# darwin-upper.net
KiCad netlist of a schematic drawn in EAGLE
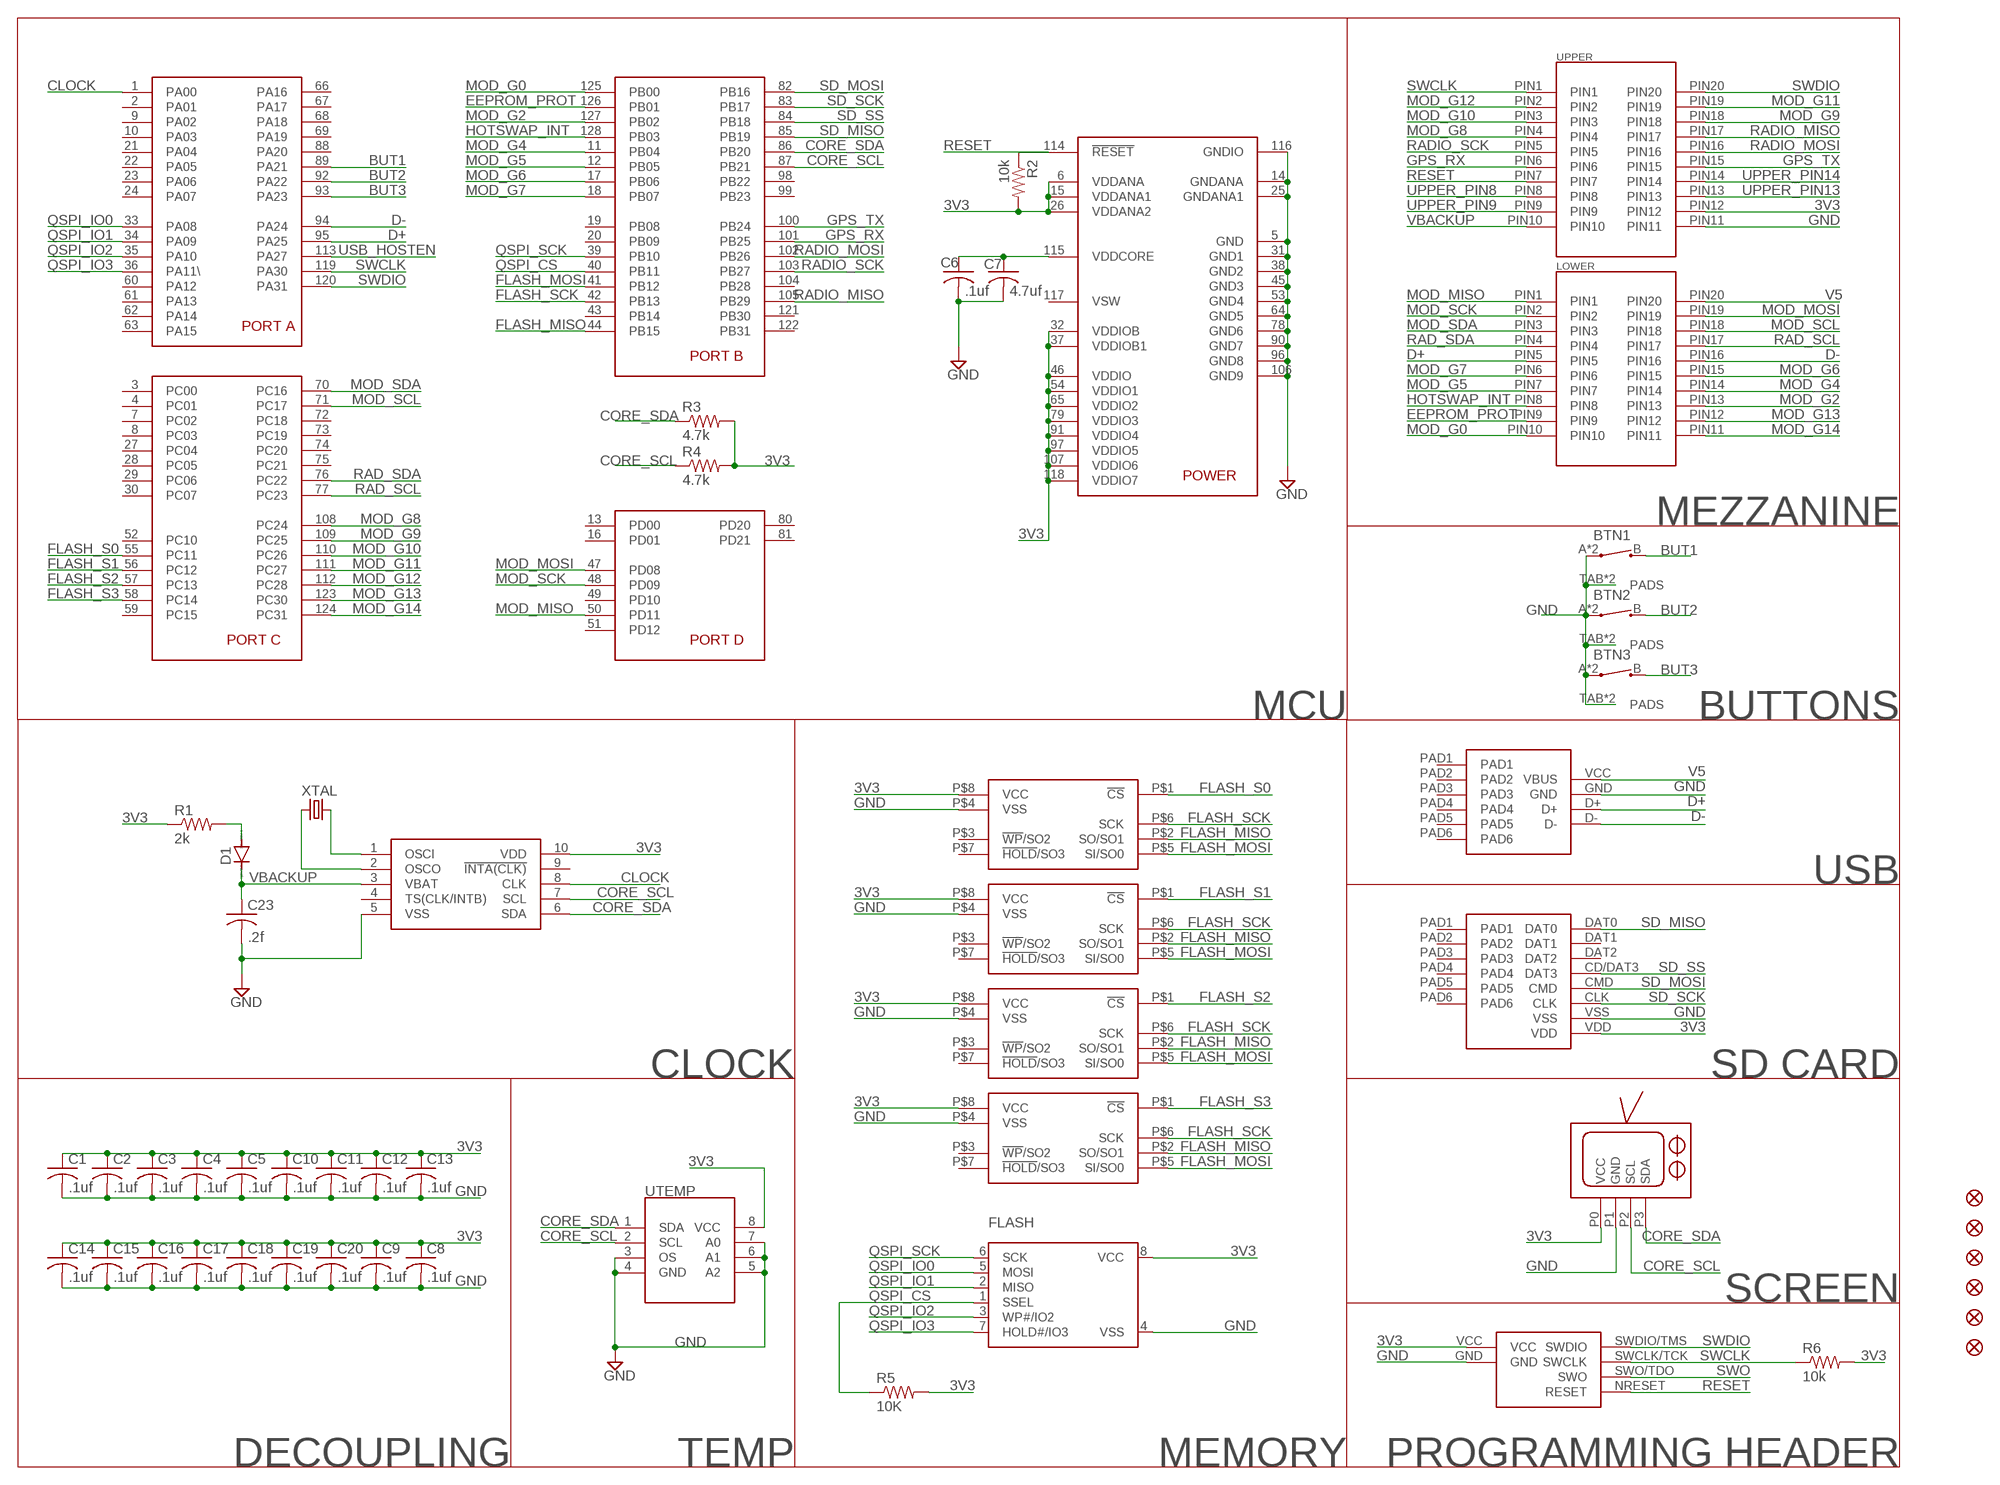
[diagram p0: schematic, sheet 1]

(export (version "E")
  (design (tool "Eeschema 10.0.6"))
  (components
    (comp (ref "BRAIN")
      (value "SAMD51PXXA")
      (footprint "eagle-import:SQFP-S-14X14-128")
      (libsource (lib "eagle-import") (part "SAMD51PXXA"))
    )
    (comp (ref "BTN1")
      (value "SKRTLAE010")
      (footprint "eagle-import:SKRTLAE010")
      (libsource (lib "eagle-import") (part "SKRTLAE010"))
    )
    (comp (ref "BTN2")
      (value "SKRTLAE010")
      (footprint "eagle-import:SKRTLAE010")
      (libsource (lib "eagle-import") (part "SKRTLAE010"))
    )
    (comp (ref "BTN3")
      (value "SKRTLAE010")
      (footprint "eagle-import:SKRTLAE010")
      (libsource (lib "eagle-import") (part "SKRTLAE010"))
    )
    (comp (ref "C1")
      (value ".1uf")
      (footprint "eagle-import:C0603K")
      (libsource (lib "eagle-import") (part "C-USC0603K"))
    )
    (comp (ref "C2")
      (value ".1uf")
      (footprint "eagle-import:C0603K")
      (libsource (lib "eagle-import") (part "C-USC0603K"))
    )
    (comp (ref "C3")
      (value ".1uf")
      (footprint "eagle-import:C0603K")
      (libsource (lib "eagle-import") (part "C-USC0603K"))
    )
    (comp (ref "C4")
      (value ".1uf")
      (footprint "eagle-import:C0603K")
      (libsource (lib "eagle-import") (part "C-USC0603K"))
    )
    (comp (ref "C5")
      (value ".1uf")
      (footprint "eagle-import:C0603K")
      (libsource (lib "eagle-import") (part "C-USC0603K"))
    )
    (comp (ref "C6")
      (value ".1uf")
      (footprint "eagle-import:C0603K")
      (libsource (lib "eagle-import") (part "C-USC0603K"))
    )
    (comp (ref "C7")
      (value "4.7uf")
      (footprint "eagle-import:C0603K")
      (libsource (lib "eagle-import") (part "C-USC0603K"))
    )
    (comp (ref "C8")
      (value ".1uf")
      (footprint "eagle-import:C0603K")
      (libsource (lib "eagle-import") (part "C-USC0603K"))
    )
    (comp (ref "C9")
      (value ".1uf")
      (footprint "eagle-import:C0603K")
      (libsource (lib "eagle-import") (part "C-USC0603K"))
    )
    (comp (ref "C10")
      (value ".1uf")
      (footprint "eagle-import:C0603K")
      (libsource (lib "eagle-import") (part "C-USC0603K"))
    )
    (comp (ref "C11")
      (value ".1uf")
      (footprint "eagle-import:C0603K")
      (libsource (lib "eagle-import") (part "C-USC0603K"))
    )
    (comp (ref "C12")
      (value ".1uf")
      (footprint "eagle-import:C0603K")
      (libsource (lib "eagle-import") (part "C-USC0603K"))
    )
    (comp (ref "C13")
      (value ".1uf")
      (footprint "eagle-import:C0603K")
      (libsource (lib "eagle-import") (part "C-USC0603K"))
    )
    (comp (ref "C14")
      (value ".1uf")
      (footprint "eagle-import:C0603K")
      (libsource (lib "eagle-import") (part "C-USC0603K"))
    )
    (comp (ref "C15")
      (value ".1uf")
      (footprint "eagle-import:C0603K")
      (libsource (lib "eagle-import") (part "C-USC0603K"))
    )
    (comp (ref "C16")
      (value ".1uf")
      (footprint "eagle-import:C0603K")
      (libsource (lib "eagle-import") (part "C-USC0603K"))
    )
    (comp (ref "C17")
      (value ".1uf")
      (footprint "eagle-import:C0603K")
      (libsource (lib "eagle-import") (part "C-USC0603K"))
    )
    (comp (ref "C18")
      (value ".1uf")
      (footprint "eagle-import:C0603K")
      (libsource (lib "eagle-import") (part "C-USC0603K"))
    )
    (comp (ref "C19")
      (value ".1uf")
      (footprint "eagle-import:C0603K")
      (libsource (lib "eagle-import") (part "C-USC0603K"))
    )
    (comp (ref "C20")
      (value ".1uf")
      (footprint "eagle-import:C0603K")
      (libsource (lib "eagle-import") (part "C-USC0603K"))
    )
    (comp (ref "C23")
      (value ".2f")
      (footprint "eagle-import:SUPERCAP")
      (libsource (lib "eagle-import") (part "DSK-3R3H204T614-H2L"))
    )
    (comp (ref "D1")
      (value "VS-10BQ015HM3/5BT")
      (footprint "eagle-import:SMB")
      (libsource (lib "eagle-import") (part "DIODE-SMB"))
    )
    (comp (ref "FID1")
      (value "FIDUCIAL_1MM")
      (footprint "eagle-import:FIDUCIAL_1MM")
      (libsource (lib "eagle-import") (part "FIDUCIAL_1MM"))
    )
    (comp (ref "FID2")
      (value "FIDUCIAL_1MM")
      (footprint "eagle-import:FIDUCIAL_1MM")
      (libsource (lib "eagle-import") (part "FIDUCIAL_1MM"))
    )
    (comp (ref "FID3")
      (value "FIDUCIAL_1MM")
      (footprint "eagle-import:FIDUCIAL_1MM")
      (libsource (lib "eagle-import") (part "FIDUCIAL_1MM"))
    )
    (comp (ref "FID4")
      (value "FIDUCIAL_1MM")
      (footprint "eagle-import:FIDUCIAL_1MM")
      (libsource (lib "eagle-import") (part "FIDUCIAL_1MM"))
    )
    (comp (ref "FID5")
      (value "FIDUCIAL_1MM")
      (footprint "eagle-import:FIDUCIAL_1MM")
      (libsource (lib "eagle-import") (part "FIDUCIAL_1MM"))
    )
    (comp (ref "FID6")
      (value "FIDUCIAL_1MM")
      (footprint "eagle-import:FIDUCIAL_1MM")
      (libsource (lib "eagle-import") (part "FIDUCIAL_1MM"))
    )
    (comp (ref "FLASH")
      (value "SPIFLASH_SOIC8208MIL")
      (footprint "eagle-import:SOIC8_208MIL")
      (libsource (lib "eagle-import") (part "SPIFLASH_SOIC8208MIL"))
    )
    (comp (ref "J1")
      (value "TAG-CONNECT")
      (footprint "eagle-import:TC2030-IDC")
      (libsource (lib "eagle-import") (part "TAG-CONNECT"))
    )
    (comp (ref "LOWER")
      (value "MOLEX-15-91-2200F")
      (footprint "eagle-import:20PH-F")
      (libsource (lib "eagle-import") (part "MOLEX-15-91-2200F"))
    )
    (comp (ref "R1")
      (value "2k")
      (footprint "eagle-import:R0603")
      (libsource (lib "eagle-import") (part "R-US_R0603"))
    )
    (comp (ref "R2")
      (value "10k")
      (footprint "eagle-import:R0603")
      (libsource (lib "eagle-import") (part "R-US_R0603"))
    )
    (comp (ref "R3")
      (value "4.7k")
      (footprint "eagle-import:R0603")
      (libsource (lib "eagle-import") (part "R-US_R0603"))
    )
    (comp (ref "R4")
      (value "4.7k")
      (footprint "eagle-import:R0603")
      (libsource (lib "eagle-import") (part "R-US_R0603"))
    )
    (comp (ref "R5")
      (value "10K")
      (footprint "eagle-import:R0603")
      (libsource (lib "eagle-import") (part "R-US_R0603"))
    )
    (comp (ref "R6")
      (value "10k")
      (footprint "eagle-import:R0603")
      (libsource (lib "eagle-import") (part "R-US_R0603"))
    )
    (comp (ref "RTC")
      (value "PCF85363ATT")
      (footprint "eagle-import:SOP50P490X110-10")
      (libsource (lib "eagle-import") (part "PCF85363ATT"))
    )
    (comp (ref "SCREEN")
      (value "SCREEN")
      (footprint "eagle-import:SCREEN")
      (libsource (lib "eagle-import") (part "SCREEN"))
    )
    (comp (ref "SD")
      (value "DM3D-SF")
      (footprint "eagle-import:DM3D-SF")
      (libsource (lib "eagle-import") (part "DM3D-SF"))
    )
    (comp (ref "U1")
      (value "TC58CVG1S3HRAIG")
      (footprint "eagle-import:WSON8")
      (libsource (lib "eagle-import") (part "TC58CVG1S3HRAIG"))
    )
    (comp (ref "U2")
      (value "TC58CVG1S3HRAIG")
      (footprint "eagle-import:WSON8")
      (libsource (lib "eagle-import") (part "TC58CVG1S3HRAIG"))
    )
    (comp (ref "U3")
      (value "TC58CVG1S3HRAIG")
      (footprint "eagle-import:WSON8")
      (libsource (lib "eagle-import") (part "TC58CVG1S3HRAIG"))
    )
    (comp (ref "U4")
      (value "TC58CVG1S3HRAIG")
      (footprint "eagle-import:WSON8")
      (libsource (lib "eagle-import") (part "TC58CVG1S3HRAIG"))
    )
    (comp (ref "UPPER")
      (value "MOLEX-15-91-2200F")
      (footprint "eagle-import:20PH-F")
      (libsource (lib "eagle-import") (part "MOLEX-15-91-2200F"))
    )
    (comp (ref "USB")
      (value "MOLEX-47491-0001")
      (footprint "eagle-import:MOELX-47491-0001")
      (libsource (lib "eagle-import") (part "MOLEX-47491-0001"))
    )
    (comp (ref "UTEMP")
      (value "PCT2075")
      (footprint "eagle-import:SO8")
      (libsource (lib "eagle-import") (part "PCT2075"))
    )
    (comp (ref "XTAL")
      (value "ABS07W")
      (footprint "eagle-import:ABS07W")
      (libsource (lib "eagle-import") (part "ABS07W"))
    )
  )
  (nets
    (net (code "1") (name "/3V3") (class "Default")
      (node (ref "BRAIN") (pin "107") (pinfunction "VDDIO6_107") (pintype "bidirectional"))
      (node (ref "BRAIN") (pin "118") (pinfunction "VDDIO7_118") (pintype "bidirectional"))
      (node (ref "BRAIN") (pin "15") (pinfunction "VDDANA1_15") (pintype "bidirectional"))
      (node (ref "BRAIN") (pin "26") (pinfunction "VDDANA2_26") (pintype "bidirectional"))
      (node (ref "BRAIN") (pin "32") (pinfunction "VDDIOB_32") (pintype "bidirectional"))
      (node (ref "BRAIN") (pin "37") (pinfunction "VDDIOB1_37") (pintype "bidirectional"))
      (node (ref "BRAIN") (pin "46") (pinfunction "VDDIO_46") (pintype "bidirectional"))
      (node (ref "BRAIN") (pin "54") (pinfunction "VDDIO1_54") (pintype "bidirectional"))
      (node (ref "BRAIN") (pin "6") (pinfunction "VDDANA_6") (pintype "bidirectional"))
      (node (ref "BRAIN") (pin "65") (pinfunction "VDDIO2_65") (pintype "bidirectional"))
      (node (ref "BRAIN") (pin "79") (pinfunction "VDDIO3_79") (pintype "bidirectional"))
      (node (ref "BRAIN") (pin "91") (pinfunction "VDDIO4_91") (pintype "bidirectional"))
      (node (ref "BRAIN") (pin "97") (pinfunction "VDDIO5_97") (pintype "bidirectional"))
      (node (ref "C1") (pin "1") (pinfunction "1_1") (pintype "passive"))
      (node (ref "C10") (pin "1") (pinfunction "1_1") (pintype "passive"))
      (node (ref "C11") (pin "1") (pinfunction "1_1") (pintype "passive"))
      (node (ref "C12") (pin "1") (pinfunction "1_1") (pintype "passive"))
      (node (ref "C13") (pin "1") (pinfunction "1_1") (pintype "passive"))
      (node (ref "C14") (pin "1") (pinfunction "1_1") (pintype "passive"))
      (node (ref "C15") (pin "1") (pinfunction "1_1") (pintype "passive"))
      (node (ref "C16") (pin "1") (pinfunction "1_1") (pintype "passive"))
      (node (ref "C17") (pin "1") (pinfunction "1_1") (pintype "passive"))
      (node (ref "C18") (pin "1") (pinfunction "1_1") (pintype "passive"))
      (node (ref "C19") (pin "1") (pinfunction "1_1") (pintype "passive"))
      (node (ref "C2") (pin "1") (pinfunction "1_1") (pintype "passive"))
      (node (ref "C20") (pin "1") (pinfunction "1_1") (pintype "passive"))
      (node (ref "C3") (pin "1") (pinfunction "1_1") (pintype "passive"))
      (node (ref "C4") (pin "1") (pinfunction "1_1") (pintype "passive"))
      (node (ref "C5") (pin "1") (pinfunction "1_1") (pintype "passive"))
      (node (ref "C8") (pin "1") (pinfunction "1_1") (pintype "passive"))
      (node (ref "C9") (pin "1") (pinfunction "1_1") (pintype "passive"))
      (node (ref "FLASH") (pin "8") (pinfunction "VCC_8") (pintype "bidirectional"))
      (node (ref "J1") (pin "VCC") (pinfunction "VCC_VCC") (pintype "bidirectional"))
      (node (ref "R1") (pin "1") (pinfunction "1_1") (pintype "passive"))
      (node (ref "R2") (pin "2") (pinfunction "2_2") (pintype "passive"))
      (node (ref "R3") (pin "2") (pinfunction "2_2") (pintype "passive"))
      (node (ref "R4") (pin "2") (pinfunction "2_2") (pintype "passive"))
      (node (ref "R5") (pin "2") (pinfunction "2_2") (pintype "passive"))
      (node (ref "R6") (pin "2") (pinfunction "2_2") (pintype "passive"))
      (node (ref "RTC") (pin "10") (pinfunction "VDD_10") (pintype "bidirectional"))
      (node (ref "SCREEN") (pin "P0") (pinfunction "VCC_P0") (pintype "bidirectional"))
      (node (ref "SD") (pin "VDD") (pinfunction "VDD_VDD") (pintype "bidirectional"))
      (node (ref "U1") (pin "P$8") (pinfunction "VCC_P$8") (pintype "bidirectional"))
      (node (ref "U2") (pin "P$8") (pinfunction "VCC_P$8") (pintype "bidirectional"))
      (node (ref "U3") (pin "P$8") (pinfunction "VCC_P$8") (pintype "bidirectional"))
      (node (ref "U4") (pin "P$8") (pinfunction "VCC_P$8") (pintype "bidirectional"))
      (node (ref "UPPER") (pin "PIN12") (pinfunction "PIN12_PIN12") (pintype "bidirectional"))
      (node (ref "UTEMP") (pin "8") (pinfunction "VCC_8") (pintype "bidirectional"))
    )
    (net (code "2") (name "/BUT1") (class "Default")
      (node (ref "BRAIN") (pin "89") (pinfunction "PA21_89") (pintype "bidirectional"))
      (node (ref "BTN1") (pin "B") (pinfunction "2_B") (pintype "passive"))
    )
    (net (code "3") (name "/BUT2") (class "Default")
      (node (ref "BRAIN") (pin "92") (pinfunction "PA22_92") (pintype "bidirectional"))
      (node (ref "BTN2") (pin "B") (pinfunction "2_B") (pintype "passive"))
    )
    (net (code "4") (name "/BUT3") (class "Default")
      (node (ref "BRAIN") (pin "93") (pinfunction "PA23_93") (pintype "bidirectional"))
      (node (ref "BTN3") (pin "B") (pinfunction "2_B") (pintype "passive"))
    )
    (net (code "5") (name "/CLOCK") (class "Default")
      (node (ref "BRAIN") (pin "1") (pinfunction "PA00_1") (pintype "bidirectional"))
      (node (ref "RTC") (pin "8") (pinfunction "CLK_8") (pintype "bidirectional"))
    )
    (net (code "6") (name "/CORE_SCL") (class "Default")
      (node (ref "BRAIN") (pin "87") (pinfunction "PB21_87") (pintype "bidirectional"))
      (node (ref "R4") (pin "1") (pinfunction "1_1") (pintype "passive"))
      (node (ref "RTC") (pin "7") (pinfunction "SCL_7") (pintype "bidirectional"))
      (node (ref "SCREEN") (pin "P2") (pinfunction "SCL_P2") (pintype "bidirectional"))
      (node (ref "UTEMP") (pin "2") (pinfunction "SCL_2") (pintype "bidirectional"))
    )
    (net (code "7") (name "/CORE_SDA") (class "Default")
      (node (ref "BRAIN") (pin "86") (pinfunction "PB20_86") (pintype "bidirectional"))
      (node (ref "R3") (pin "1") (pinfunction "1_1") (pintype "passive"))
      (node (ref "RTC") (pin "6") (pinfunction "SDA_6") (pintype "bidirectional"))
      (node (ref "SCREEN") (pin "P3") (pinfunction "SDA_P3") (pintype "bidirectional"))
      (node (ref "UTEMP") (pin "1") (pinfunction "SDA_1") (pintype "bidirectional"))
    )
    (net (code "8") (name "/D+") (class "Default")
      (node (ref "BRAIN") (pin "95") (pinfunction "PA25_95") (pintype "bidirectional"))
      (node (ref "LOWER") (pin "PIN5") (pinfunction "PIN5_PIN5") (pintype "bidirectional"))
      (node (ref "USB") (pin "D+") (pinfunction "D+_D+") (pintype "bidirectional"))
    )
    (net (code "9") (name "/D-") (class "Default")
      (node (ref "BRAIN") (pin "94") (pinfunction "PA24_94") (pintype "bidirectional"))
      (node (ref "LOWER") (pin "PIN16") (pinfunction "PIN16_PIN16") (pintype "bidirectional"))
      (node (ref "USB") (pin "D-") (pinfunction "D-_D-") (pintype "bidirectional"))
    )
    (net (code "10") (name "/EEPROM_PROT") (class "Default")
      (node (ref "BRAIN") (pin "126") (pinfunction "PB01_126") (pintype "bidirectional"))
      (node (ref "LOWER") (pin "PIN9") (pinfunction "PIN9_PIN9") (pintype "bidirectional"))
    )
    (net (code "11") (name "/FLASH_MISO") (class "Default")
      (node (ref "BRAIN") (pin "44") (pinfunction "PB15_44") (pintype "bidirectional"))
      (node (ref "U1") (pin "P$2") (pinfunction "SO/SO1_P$2") (pintype "bidirectional"))
      (node (ref "U2") (pin "P$2") (pinfunction "SO/SO1_P$2") (pintype "bidirectional"))
      (node (ref "U3") (pin "P$2") (pinfunction "SO/SO1_P$2") (pintype "bidirectional"))
      (node (ref "U4") (pin "P$2") (pinfunction "SO/SO1_P$2") (pintype "bidirectional"))
    )
    (net (code "12") (name "/FLASH_MOSI") (class "Default")
      (node (ref "BRAIN") (pin "41") (pinfunction "PB12_41") (pintype "bidirectional"))
      (node (ref "U1") (pin "P$5") (pinfunction "SI/SO0_P$5") (pintype "bidirectional"))
      (node (ref "U2") (pin "P$5") (pinfunction "SI/SO0_P$5") (pintype "bidirectional"))
      (node (ref "U3") (pin "P$5") (pinfunction "SI/SO0_P$5") (pintype "bidirectional"))
      (node (ref "U4") (pin "P$5") (pinfunction "SI/SO0_P$5") (pintype "bidirectional"))
    )
    (net (code "13") (name "/FLASH_S0") (class "Default")
      (node (ref "BRAIN") (pin "55") (pinfunction "PC11_55") (pintype "bidirectional"))
      (node (ref "U1") (pin "P$1") (pinfunction "~{CS}_P$1") (pintype "bidirectional"))
    )
    (net (code "14") (name "/FLASH_S1") (class "Default")
      (node (ref "BRAIN") (pin "56") (pinfunction "PC12_56") (pintype "bidirectional"))
      (node (ref "U2") (pin "P$1") (pinfunction "~{CS}_P$1") (pintype "bidirectional"))
    )
    (net (code "15") (name "/FLASH_S2") (class "Default")
      (node (ref "BRAIN") (pin "57") (pinfunction "PC13_57") (pintype "bidirectional"))
      (node (ref "U3") (pin "P$1") (pinfunction "~{CS}_P$1") (pintype "bidirectional"))
    )
    (net (code "16") (name "/FLASH_S3") (class "Default")
      (node (ref "BRAIN") (pin "58") (pinfunction "PC14_58") (pintype "bidirectional"))
      (node (ref "U4") (pin "P$1") (pinfunction "~{CS}_P$1") (pintype "bidirectional"))
    )
    (net (code "17") (name "/FLASH_SCK") (class "Default")
      (node (ref "BRAIN") (pin "42") (pinfunction "PB13_42") (pintype "bidirectional"))
      (node (ref "U1") (pin "P$6") (pinfunction "SCK_P$6") (pintype "bidirectional"))
      (node (ref "U2") (pin "P$6") (pinfunction "SCK_P$6") (pintype "bidirectional"))
      (node (ref "U3") (pin "P$6") (pinfunction "SCK_P$6") (pintype "bidirectional"))
      (node (ref "U4") (pin "P$6") (pinfunction "SCK_P$6") (pintype "bidirectional"))
    )
    (net (code "18") (name "/GPS_RX") (class "Default")
      (node (ref "BRAIN") (pin "101") (pinfunction "PB25_101") (pintype "bidirectional"))
      (node (ref "UPPER") (pin "PIN6") (pinfunction "PIN6_PIN6") (pintype "bidirectional"))
    )
    (net (code "19") (name "/GPS_TX") (class "Default")
      (node (ref "BRAIN") (pin "100") (pinfunction "PB24_100") (pintype "bidirectional"))
      (node (ref "UPPER") (pin "PIN15") (pinfunction "PIN15_PIN15") (pintype "bidirectional"))
    )
    (net (code "20") (name "/HOTSWAP_INT") (class "Default")
      (node (ref "BRAIN") (pin "128") (pinfunction "PB03_128") (pintype "bidirectional"))
      (node (ref "LOWER") (pin "PIN8") (pinfunction "PIN8_PIN8") (pintype "bidirectional"))
    )
    (net (code "21") (name "/MOD_G0") (class "Default")
      (node (ref "BRAIN") (pin "125") (pinfunction "PB00_125") (pintype "bidirectional"))
      (node (ref "LOWER") (pin "PIN10") (pinfunction "PIN10_PIN10") (pintype "bidirectional"))
    )
    (net (code "22") (name "/MOD_G2") (class "Default")
      (node (ref "BRAIN") (pin "127") (pinfunction "PB02_127") (pintype "bidirectional"))
      (node (ref "LOWER") (pin "PIN13") (pinfunction "PIN13_PIN13") (pintype "bidirectional"))
    )
    (net (code "23") (name "/MOD_G4") (class "Default")
      (node (ref "BRAIN") (pin "11") (pinfunction "PB04_11") (pintype "bidirectional"))
      (node (ref "LOWER") (pin "PIN14") (pinfunction "PIN14_PIN14") (pintype "bidirectional"))
    )
    (net (code "24") (name "/MOD_G5") (class "Default")
      (node (ref "BRAIN") (pin "12") (pinfunction "PB05_12") (pintype "bidirectional"))
      (node (ref "LOWER") (pin "PIN7") (pinfunction "PIN7_PIN7") (pintype "bidirectional"))
    )
    (net (code "25") (name "/MOD_G6") (class "Default")
      (node (ref "BRAIN") (pin "17") (pinfunction "PB06_17") (pintype "bidirectional"))
      (node (ref "LOWER") (pin "PIN15") (pinfunction "PIN15_PIN15") (pintype "bidirectional"))
    )
    (net (code "26") (name "/MOD_G7") (class "Default")
      (node (ref "BRAIN") (pin "18") (pinfunction "PB07_18") (pintype "bidirectional"))
      (node (ref "LOWER") (pin "PIN6") (pinfunction "PIN6_PIN6") (pintype "bidirectional"))
    )
    (net (code "27") (name "/MOD_G8") (class "Default")
      (node (ref "BRAIN") (pin "108") (pinfunction "PC24_108") (pintype "bidirectional"))
      (node (ref "UPPER") (pin "PIN4") (pinfunction "PIN4_PIN4") (pintype "bidirectional"))
    )
    (net (code "28") (name "/MOD_G9") (class "Default")
      (node (ref "BRAIN") (pin "109") (pinfunction "PC25_109") (pintype "bidirectional"))
      (node (ref "UPPER") (pin "PIN18") (pinfunction "PIN18_PIN18") (pintype "bidirectional"))
    )
    (net (code "29") (name "/MOD_G10") (class "Default")
      (node (ref "BRAIN") (pin "110") (pinfunction "PC26_110") (pintype "bidirectional"))
      (node (ref "UPPER") (pin "PIN3") (pinfunction "PIN3_PIN3") (pintype "bidirectional"))
    )
    (net (code "30") (name "/MOD_G11") (class "Default")
      (node (ref "BRAIN") (pin "111") (pinfunction "PC27_111") (pintype "bidirectional"))
      (node (ref "UPPER") (pin "PIN19") (pinfunction "PIN19_PIN19") (pintype "bidirectional"))
    )
    (net (code "31") (name "/MOD_G12") (class "Default")
      (node (ref "BRAIN") (pin "112") (pinfunction "PC28_112") (pintype "bidirectional"))
      (node (ref "UPPER") (pin "PIN2") (pinfunction "PIN2_PIN2") (pintype "bidirectional"))
    )
    (net (code "32") (name "/MOD_G13") (class "Default")
      (node (ref "BRAIN") (pin "123") (pinfunction "PC30_123") (pintype "bidirectional"))
      (node (ref "LOWER") (pin "PIN12") (pinfunction "PIN12_PIN12") (pintype "bidirectional"))
    )
    (net (code "33") (name "/MOD_G14") (class "Default")
      (node (ref "BRAIN") (pin "124") (pinfunction "PC31_124") (pintype "bidirectional"))
      (node (ref "LOWER") (pin "PIN11") (pinfunction "PIN11_PIN11") (pintype "bidirectional"))
    )
    (net (code "34") (name "/MOD_MISO") (class "Default")
      (node (ref "BRAIN") (pin "50") (pinfunction "PD11_50") (pintype "bidirectional"))
      (node (ref "LOWER") (pin "PIN1") (pinfunction "PIN1_PIN1") (pintype "bidirectional"))
    )
    (net (code "35") (name "/MOD_MOSI") (class "Default")
      (node (ref "BRAIN") (pin "47") (pinfunction "PD08_47") (pintype "bidirectional"))
      (node (ref "LOWER") (pin "PIN19") (pinfunction "PIN19_PIN19") (pintype "bidirectional"))
    )
    (net (code "36") (name "/MOD_SCK") (class "Default")
      (node (ref "BRAIN") (pin "48") (pinfunction "PD09_48") (pintype "bidirectional"))
      (node (ref "LOWER") (pin "PIN2") (pinfunction "PIN2_PIN2") (pintype "bidirectional"))
    )
    (net (code "37") (name "/MOD_SCL") (class "Default")
      (node (ref "BRAIN") (pin "71") (pinfunction "PC17_71") (pintype "bidirectional"))
      (node (ref "LOWER") (pin "PIN18") (pinfunction "PIN18_PIN18") (pintype "bidirectional"))
    )
    (net (code "38") (name "/MOD_SDA") (class "Default")
      (node (ref "BRAIN") (pin "70") (pinfunction "PC16_70") (pintype "bidirectional"))
      (node (ref "LOWER") (pin "PIN3") (pinfunction "PIN3_PIN3") (pintype "bidirectional"))
    )
    (net (code "39") (name "/QSPI_CS") (class "Default")
      (node (ref "BRAIN") (pin "40") (pinfunction "PB11_40") (pintype "bidirectional"))
      (node (ref "FLASH") (pin "1") (pinfunction "SSEL_1") (pintype "bidirectional"))
      (node (ref "R5") (pin "1") (pinfunction "1_1") (pintype "passive"))
    )
    (net (code "40") (name "/QSPI_IO0") (class "Default")
      (node (ref "BRAIN") (pin "33") (pinfunction "PA08_33") (pintype "bidirectional"))
      (node (ref "FLASH") (pin "5") (pinfunction "MOSI_5") (pintype "bidirectional"))
    )
    (net (code "41") (name "/QSPI_IO1") (class "Default")
      (node (ref "BRAIN") (pin "34") (pinfunction "PA09_34") (pintype "bidirectional"))
      (node (ref "FLASH") (pin "2") (pinfunction "MISO_2") (pintype "bidirectional"))
    )
    (net (code "42") (name "/QSPI_IO2") (class "Default")
      (node (ref "BRAIN") (pin "35") (pinfunction "PA10_35") (pintype "bidirectional"))
      (node (ref "FLASH") (pin "3") (pinfunction "WP#/IO2_3") (pintype "bidirectional"))
    )
    (net (code "43") (name "/QSPI_IO3") (class "Default")
      (node (ref "BRAIN") (pin "36") (pinfunction "PA11\\_36") (pintype "bidirectional"))
      (node (ref "FLASH") (pin "7") (pinfunction "HOLD#/IO3_7") (pintype "bidirectional"))
    )
    (net (code "44") (name "/QSPI_SCK") (class "Default")
      (node (ref "BRAIN") (pin "39") (pinfunction "PB10_39") (pintype "bidirectional"))
      (node (ref "FLASH") (pin "6") (pinfunction "SCK_6") (pintype "bidirectional"))
    )
    (net (code "45") (name "/RADIO_MISO") (class "Default")
      (node (ref "BRAIN") (pin "105") (pinfunction "PB29_105") (pintype "bidirectional"))
      (node (ref "UPPER") (pin "PIN17") (pinfunction "PIN17_PIN17") (pintype "bidirectional"))
    )
    (net (code "46") (name "/RADIO_MOSI") (class "Default")
      (node (ref "BRAIN") (pin "102") (pinfunction "PB26_102") (pintype "bidirectional"))
      (node (ref "UPPER") (pin "PIN16") (pinfunction "PIN16_PIN16") (pintype "bidirectional"))
    )
    (net (code "47") (name "/RADIO_SCK") (class "Default")
      (node (ref "BRAIN") (pin "103") (pinfunction "PB27_103") (pintype "bidirectional"))
      (node (ref "UPPER") (pin "PIN5") (pinfunction "PIN5_PIN5") (pintype "bidirectional"))
    )
    (net (code "48") (name "/RAD_SCL") (class "Default")
      (node (ref "BRAIN") (pin "77") (pinfunction "PC23_77") (pintype "bidirectional"))
      (node (ref "LOWER") (pin "PIN17") (pinfunction "PIN17_PIN17") (pintype "bidirectional"))
    )
    (net (code "49") (name "/RAD_SDA") (class "Default")
      (node (ref "BRAIN") (pin "76") (pinfunction "PC22_76") (pintype "bidirectional"))
      (node (ref "LOWER") (pin "PIN4") (pinfunction "PIN4_PIN4") (pintype "bidirectional"))
    )
    (net (code "50") (name "/RESET") (class "Default")
      (node (ref "BRAIN") (pin "114") (pinfunction "~{RESET}_114") (pintype "bidirectional"))
      (node (ref "J1") (pin "NRESET") (pinfunction "RESET_NRESET") (pintype "bidirectional"))
      (node (ref "R2") (pin "1") (pinfunction "1_1") (pintype "passive"))
      (node (ref "UPPER") (pin "PIN7") (pinfunction "PIN7_PIN7") (pintype "bidirectional"))
    )
    (net (code "51") (name "/SD_MISO") (class "Default")
      (node (ref "BRAIN") (pin "85") (pinfunction "PB19_85") (pintype "bidirectional"))
      (node (ref "SD") (pin "DAT0") (pinfunction "DAT0_DAT0") (pintype "bidirectional"))
    )
    (net (code "52") (name "/SD_MOSI") (class "Default")
      (node (ref "BRAIN") (pin "82") (pinfunction "PB16_82") (pintype "bidirectional"))
      (node (ref "SD") (pin "CMD") (pinfunction "CMD_CMD") (pintype "bidirectional"))
    )
    (net (code "53") (name "/SD_SCK") (class "Default")
      (node (ref "BRAIN") (pin "83") (pinfunction "PB17_83") (pintype "bidirectional"))
      (node (ref "SD") (pin "CLK") (pinfunction "CLK_CLK") (pintype "bidirectional"))
    )
    (net (code "54") (name "/SD_SS") (class "Default")
      (node (ref "BRAIN") (pin "84") (pinfunction "PB18_84") (pintype "bidirectional"))
      (node (ref "SD") (pin "CD/DAT3") (pinfunction "DAT3_CD/DAT3") (pintype "bidirectional"))
    )
    (net (code "55") (name "/SWCLK") (class "Default")
      (node (ref "BRAIN") (pin "119") (pinfunction "PA30_119") (pintype "bidirectional"))
      (node (ref "J1") (pin "SWCLK/TCK") (pinfunction "SWCLK_SWCLK/TCK") (pintype "bidirectional"))
      (node (ref "R6") (pin "1") (pinfunction "1_1") (pintype "passive"))
      (node (ref "UPPER") (pin "PIN1") (pinfunction "PIN1_PIN1") (pintype "bidirectional"))
    )
    (net (code "56") (name "/SWDIO") (class "Default")
      (node (ref "BRAIN") (pin "120") (pinfunction "PA31_120") (pintype "bidirectional"))
      (node (ref "J1") (pin "SWDIO/TMS") (pinfunction "SWDIO_SWDIO/TMS") (pintype "bidirectional"))
      (node (ref "UPPER") (pin "PIN20") (pinfunction "PIN20_PIN20") (pintype "bidirectional"))
    )
    (net (code "57") (name "/SWO") (class "Default")
      (node (ref "J1") (pin "SWO/TDO") (pinfunction "SWO_SWO/TDO") (pintype "bidirectional"))
    )
    (net (code "58") (name "/UPPER_PIN8") (class "Default")
      (node (ref "UPPER") (pin "PIN8") (pinfunction "PIN8_PIN8") (pintype "bidirectional"))
    )
    (net (code "59") (name "/UPPER_PIN9") (class "Default")
      (node (ref "UPPER") (pin "PIN9") (pinfunction "PIN9_PIN9") (pintype "bidirectional"))
    )
    (net (code "60") (name "/UPPER_PIN13") (class "Default")
      (node (ref "UPPER") (pin "PIN13") (pinfunction "PIN13_PIN13") (pintype "bidirectional"))
    )
    (net (code "61") (name "/UPPER_PIN14") (class "Default")
      (node (ref "UPPER") (pin "PIN14") (pinfunction "PIN14_PIN14") (pintype "bidirectional"))
    )
    (net (code "62") (name "/USB_HOSTEN") (class "Default")
      (node (ref "BRAIN") (pin "113") (pinfunction "PA27_113") (pintype "bidirectional"))
    )
    (net (code "63") (name "/V5") (class "Default")
      (node (ref "LOWER") (pin "PIN20") (pinfunction "PIN20_PIN20") (pintype "bidirectional"))
      (node (ref "USB") (pin "VCC") (pinfunction "VBUS_VCC") (pintype "bidirectional"))
    )
    (net (code "64") (name "/VBACKUP") (class "Default")
      (node (ref "C23") (pin "+") (pinfunction "+_+") (pintype "passive"))
      (node (ref "D1") (pin "C") (pinfunction "C_C") (pintype "passive"))
      (node (ref "RTC") (pin "3") (pinfunction "VBAT_3") (pintype "bidirectional"))
      (node (ref "UPPER") (pin "PIN10") (pinfunction "PIN10_PIN10") (pintype "bidirectional"))
    )
    (net (code "65") (name "GND") (class "Default")
      (node (ref "BRAIN") (pin "106") (pinfunction "GND9_106") (pintype "bidirectional"))
      (node (ref "BRAIN") (pin "116") (pinfunction "GNDIO_116") (pintype "bidirectional"))
      (node (ref "BRAIN") (pin "14") (pinfunction "GNDANA_14") (pintype "bidirectional"))
      (node (ref "BRAIN") (pin "25") (pinfunction "GNDANA1_25") (pintype "bidirectional"))
      (node (ref "BRAIN") (pin "31") (pinfunction "GND1_31") (pintype "bidirectional"))
      (node (ref "BRAIN") (pin "38") (pinfunction "GND2_38") (pintype "bidirectional"))
      (node (ref "BRAIN") (pin "45") (pinfunction "GND3_45") (pintype "bidirectional"))
      (node (ref "BRAIN") (pin "5") (pinfunction "GND_5") (pintype "bidirectional"))
      (node (ref "BRAIN") (pin "53") (pinfunction "GND4_53") (pintype "bidirectional"))
      (node (ref "BRAIN") (pin "64") (pinfunction "GND5_64") (pintype "bidirectional"))
      (node (ref "BRAIN") (pin "78") (pinfunction "GND6_78") (pintype "bidirectional"))
      (node (ref "BRAIN") (pin "90") (pinfunction "GND7_90") (pintype "bidirectional"))
      (node (ref "BRAIN") (pin "96") (pinfunction "GND8_96") (pintype "bidirectional"))
      (node (ref "BTN1") (pin "A") (pinfunction "1_A") (pintype "passive"))
      (node (ref "BTN1") (pin "A2") (pinfunction "1_A2") (pintype "passive"))
      (node (ref "BTN1") (pin "TAB") (pinfunction "PADS_TAB") (pintype "bidirectional"))
      (node (ref "BTN1") (pin "TAB2") (pinfunction "PADS_TAB2") (pintype "bidirectional"))
      (node (ref "BTN2") (pin "A") (pinfunction "1_A") (pintype "passive"))
      (node (ref "BTN2") (pin "A2") (pinfunction "1_A2") (pintype "passive"))
      (node (ref "BTN2") (pin "TAB") (pinfunction "PADS_TAB") (pintype "bidirectional"))
      (node (ref "BTN2") (pin "TAB2") (pinfunction "PADS_TAB2") (pintype "bidirectional"))
      (node (ref "BTN3") (pin "A") (pinfunction "1_A") (pintype "passive"))
      (node (ref "BTN3") (pin "A2") (pinfunction "1_A2") (pintype "passive"))
      (node (ref "BTN3") (pin "TAB") (pinfunction "PADS_TAB") (pintype "bidirectional"))
      (node (ref "BTN3") (pin "TAB2") (pinfunction "PADS_TAB2") (pintype "bidirectional"))
      (node (ref "C1") (pin "2") (pinfunction "2_2") (pintype "passive"))
      (node (ref "C10") (pin "2") (pinfunction "2_2") (pintype "passive"))
      (node (ref "C11") (pin "2") (pinfunction "2_2") (pintype "passive"))
      (node (ref "C12") (pin "2") (pinfunction "2_2") (pintype "passive"))
      (node (ref "C13") (pin "2") (pinfunction "2_2") (pintype "passive"))
      (node (ref "C14") (pin "2") (pinfunction "2_2") (pintype "passive"))
      (node (ref "C15") (pin "2") (pinfunction "2_2") (pintype "passive"))
      (node (ref "C16") (pin "2") (pinfunction "2_2") (pintype "passive"))
      (node (ref "C17") (pin "2") (pinfunction "2_2") (pintype "passive"))
      (node (ref "C18") (pin "2") (pinfunction "2_2") (pintype "passive"))
      (node (ref "C19") (pin "2") (pinfunction "2_2") (pintype "passive"))
      (node (ref "C2") (pin "2") (pinfunction "2_2") (pintype "passive"))
      (node (ref "C20") (pin "2") (pinfunction "2_2") (pintype "passive"))
      (node (ref "C23") (pin "-") (pinfunction "-_-") (pintype "passive"))
      (node (ref "C3") (pin "2") (pinfunction "2_2") (pintype "passive"))
      (node (ref "C4") (pin "2") (pinfunction "2_2") (pintype "passive"))
      (node (ref "C5") (pin "2") (pinfunction "2_2") (pintype "passive"))
      (node (ref "C6") (pin "2") (pinfunction "2_2") (pintype "passive"))
      (node (ref "C7") (pin "2") (pinfunction "2_2") (pintype "passive"))
      (node (ref "C8") (pin "2") (pinfunction "2_2") (pintype "passive"))
      (node (ref "C9") (pin "2") (pinfunction "2_2") (pintype "passive"))
      (node (ref "FLASH") (pin "4") (pinfunction "VSS_4") (pintype "bidirectional"))
      (node (ref "J1") (pin "GND") (pinfunction "GND_GND") (pintype "bidirectional"))
      (node (ref "RTC") (pin "5") (pinfunction "VSS_5") (pintype "bidirectional"))
      (node (ref "SCREEN") (pin "P1") (pinfunction "GND_P1") (pintype "bidirectional"))
      (node (ref "SD") (pin "VSS") (pinfunction "VSS_VSS") (pintype "bidirectional"))
      (node (ref "U1") (pin "P$4") (pinfunction "VSS_P$4") (pintype "bidirectional"))
      (node (ref "U2") (pin "P$4") (pinfunction "VSS_P$4") (pintype "bidirectional"))
      (node (ref "U3") (pin "P$4") (pinfunction "VSS_P$4") (pintype "bidirectional"))
      (node (ref "U4") (pin "P$4") (pinfunction "VSS_P$4") (pintype "bidirectional"))
      (node (ref "UPPER") (pin "PIN11") (pinfunction "PIN11_PIN11") (pintype "bidirectional"))
      (node (ref "USB") (pin "GND") (pinfunction "GND_GND") (pintype "bidirectional"))
      (node (ref "UTEMP") (pin "3") (pinfunction "OS_3") (pintype "bidirectional"))
      (node (ref "UTEMP") (pin "4") (pinfunction "GND_4") (pintype "bidirectional"))
      (node (ref "UTEMP") (pin "5") (pinfunction "A2_5") (pintype "bidirectional"))
      (node (ref "UTEMP") (pin "6") (pinfunction "A1_6") (pintype "bidirectional"))
      (node (ref "UTEMP") (pin "7") (pinfunction "A0_7") (pintype "bidirectional"))
    )
    (net (code "66") (name "Net-(BRAINE-VDDCORE)") (class "Default")
      (node (ref "BRAIN") (pin "115") (pinfunction "VDDCORE_115") (pintype "bidirectional"))
      (node (ref "C6") (pin "1") (pinfunction "1_1") (pintype "passive"))
      (node (ref "C7") (pin "1") (pinfunction "1_1") (pintype "passive"))
    )
    (net (code "67") (name "Net-(D1-PadA)") (class "Default")
      (node (ref "D1") (pin "A") (pinfunction "A_A") (pintype "passive"))
      (node (ref "R1") (pin "2") (pinfunction "2_2") (pintype "passive"))
    )
    (net (code "68") (name "Net-(RTC-OSCI)") (class "Default")
      (node (ref "RTC") (pin "1") (pinfunction "OSCI_1") (pintype "bidirectional"))
      (node (ref "XTAL") (pin "P$2") (pinfunction "2_P$2") (pintype "passive"))
    )
    (net (code "69") (name "Net-(RTC-OSCO)") (class "Default")
      (node (ref "RTC") (pin "2") (pinfunction "OSCO_2") (pintype "bidirectional"))
      (node (ref "XTAL") (pin "P$1") (pinfunction "1_P$1") (pintype "passive"))
    )
    (net (code "70") (name "unconnected-(BRAINA-PA01-Pad2)") (class "Default")
      (node (ref "BRAIN") (pin "2") (pinfunction "PA01_2") (pintype "bidirectional"))
    )
    (net (code "71") (name "unconnected-(BRAINA-PA02-Pad9)") (class "Default")
      (node (ref "BRAIN") (pin "9") (pinfunction "PA02_9") (pintype "bidirectional"))
    )
    (net (code "72") (name "unconnected-(BRAINA-PA03-Pad10)") (class "Default")
      (node (ref "BRAIN") (pin "10") (pinfunction "PA03_10") (pintype "bidirectional"))
    )
    (net (code "73") (name "unconnected-(BRAINA-PA04-Pad21)") (class "Default")
      (node (ref "BRAIN") (pin "21") (pinfunction "PA04_21") (pintype "bidirectional"))
    )
    (net (code "74") (name "unconnected-(BRAINA-PA05-Pad22)") (class "Default")
      (node (ref "BRAIN") (pin "22") (pinfunction "PA05_22") (pintype "bidirectional"))
    )
    (net (code "75") (name "unconnected-(BRAINA-PA06-Pad23)") (class "Default")
      (node (ref "BRAIN") (pin "23") (pinfunction "PA06_23") (pintype "bidirectional"))
    )
    (net (code "76") (name "unconnected-(BRAINA-PA07-Pad24)") (class "Default")
      (node (ref "BRAIN") (pin "24") (pinfunction "PA07_24") (pintype "bidirectional"))
    )
    (net (code "77") (name "unconnected-(BRAINA-PA12-Pad60)") (class "Default")
      (node (ref "BRAIN") (pin "60") (pinfunction "PA12_60") (pintype "bidirectional"))
    )
    (net (code "78") (name "unconnected-(BRAINA-PA13-Pad61)") (class "Default")
      (node (ref "BRAIN") (pin "61") (pinfunction "PA13_61") (pintype "bidirectional"))
    )
    (net (code "79") (name "unconnected-(BRAINA-PA14-Pad62)") (class "Default")
      (node (ref "BRAIN") (pin "62") (pinfunction "PA14_62") (pintype "bidirectional"))
    )
    (net (code "80") (name "unconnected-(BRAINA-PA15-Pad63)") (class "Default")
      (node (ref "BRAIN") (pin "63") (pinfunction "PA15_63") (pintype "bidirectional"))
    )
    (net (code "81") (name "unconnected-(BRAINA-PA16-Pad66)") (class "Default")
      (node (ref "BRAIN") (pin "66") (pinfunction "PA16_66") (pintype "bidirectional"))
    )
    (net (code "82") (name "unconnected-(BRAINA-PA17-Pad67)") (class "Default")
      (node (ref "BRAIN") (pin "67") (pinfunction "PA17_67") (pintype "bidirectional"))
    )
    (net (code "83") (name "unconnected-(BRAINA-PA18-Pad68)") (class "Default")
      (node (ref "BRAIN") (pin "68") (pinfunction "PA18_68") (pintype "bidirectional"))
    )
    (net (code "84") (name "unconnected-(BRAINA-PA19-Pad69)") (class "Default")
      (node (ref "BRAIN") (pin "69") (pinfunction "PA19_69") (pintype "bidirectional"))
    )
    (net (code "85") (name "unconnected-(BRAINA-PA20-Pad88)") (class "Default")
      (node (ref "BRAIN") (pin "88") (pinfunction "PA20_88") (pintype "bidirectional"))
    )
    (net (code "86") (name "unconnected-(BRAINB-PB08-Pad19)") (class "Default")
      (node (ref "BRAIN") (pin "19") (pinfunction "PB08_19") (pintype "bidirectional"))
    )
    (net (code "87") (name "unconnected-(BRAINB-PB09-Pad20)") (class "Default")
      (node (ref "BRAIN") (pin "20") (pinfunction "PB09_20") (pintype "bidirectional"))
    )
    (net (code "88") (name "unconnected-(BRAINB-PB14-Pad43)") (class "Default")
      (node (ref "BRAIN") (pin "43") (pinfunction "PB14_43") (pintype "bidirectional"))
    )
    (net (code "89") (name "unconnected-(BRAINB-PB22-Pad98)") (class "Default")
      (node (ref "BRAIN") (pin "98") (pinfunction "PB22_98") (pintype "bidirectional"))
    )
    (net (code "90") (name "unconnected-(BRAINB-PB23-Pad99)") (class "Default")
      (node (ref "BRAIN") (pin "99") (pinfunction "PB23_99") (pintype "bidirectional"))
    )
    (net (code "91") (name "unconnected-(BRAINB-PB28-Pad104)") (class "Default")
      (node (ref "BRAIN") (pin "104") (pinfunction "PB28_104") (pintype "bidirectional"))
    )
    (net (code "92") (name "unconnected-(BRAINB-PB30-Pad121)") (class "Default")
      (node (ref "BRAIN") (pin "121") (pinfunction "PB30_121") (pintype "bidirectional"))
    )
    (net (code "93") (name "unconnected-(BRAINB-PB31-Pad122)") (class "Default")
      (node (ref "BRAIN") (pin "122") (pinfunction "PB31_122") (pintype "bidirectional"))
    )
    (net (code "94") (name "unconnected-(BRAINC-PC00-Pad3)") (class "Default")
      (node (ref "BRAIN") (pin "3") (pinfunction "PC00_3") (pintype "bidirectional"))
    )
    (net (code "95") (name "unconnected-(BRAINC-PC01-Pad4)") (class "Default")
      (node (ref "BRAIN") (pin "4") (pinfunction "PC01_4") (pintype "bidirectional"))
    )
    (net (code "96") (name "unconnected-(BRAINC-PC02-Pad7)") (class "Default")
      (node (ref "BRAIN") (pin "7") (pinfunction "PC02_7") (pintype "bidirectional"))
    )
    (net (code "97") (name "unconnected-(BRAINC-PC03-Pad8)") (class "Default")
      (node (ref "BRAIN") (pin "8") (pinfunction "PC03_8") (pintype "bidirectional"))
    )
    (net (code "98") (name "unconnected-(BRAINC-PC04-Pad27)") (class "Default")
      (node (ref "BRAIN") (pin "27") (pinfunction "PC04_27") (pintype "bidirectional"))
    )
    (net (code "99") (name "unconnected-(BRAINC-PC05-Pad28)") (class "Default")
      (node (ref "BRAIN") (pin "28") (pinfunction "PC05_28") (pintype "bidirectional"))
    )
    (net (code "100") (name "unconnected-(BRAINC-PC06-Pad29)") (class "Default")
      (node (ref "BRAIN") (pin "29") (pinfunction "PC06_29") (pintype "bidirectional"))
    )
    (net (code "101") (name "unconnected-(BRAINC-PC07-Pad30)") (class "Default")
      (node (ref "BRAIN") (pin "30") (pinfunction "PC07_30") (pintype "bidirectional"))
    )
    (net (code "102") (name "unconnected-(BRAINC-PC10-Pad52)") (class "Default")
      (node (ref "BRAIN") (pin "52") (pinfunction "PC10_52") (pintype "bidirectional"))
    )
    (net (code "103") (name "unconnected-(BRAINC-PC15-Pad59)") (class "Default")
      (node (ref "BRAIN") (pin "59") (pinfunction "PC15_59") (pintype "bidirectional"))
    )
    (net (code "104") (name "unconnected-(BRAINC-PC18-Pad72)") (class "Default")
      (node (ref "BRAIN") (pin "72") (pinfunction "PC18_72") (pintype "bidirectional"))
    )
    (net (code "105") (name "unconnected-(BRAINC-PC19-Pad73)") (class "Default")
      (node (ref "BRAIN") (pin "73") (pinfunction "PC19_73") (pintype "bidirectional"))
    )
    (net (code "106") (name "unconnected-(BRAINC-PC20-Pad74)") (class "Default")
      (node (ref "BRAIN") (pin "74") (pinfunction "PC20_74") (pintype "bidirectional"))
    )
    (net (code "107") (name "unconnected-(BRAINC-PC21-Pad75)") (class "Default")
      (node (ref "BRAIN") (pin "75") (pinfunction "PC21_75") (pintype "bidirectional"))
    )
    (net (code "108") (name "unconnected-(BRAIND-PD00-Pad13)") (class "Default")
      (node (ref "BRAIN") (pin "13") (pinfunction "PD00_13") (pintype "bidirectional"))
    )
    (net (code "109") (name "unconnected-(BRAIND-PD01-Pad16)") (class "Default")
      (node (ref "BRAIN") (pin "16") (pinfunction "PD01_16") (pintype "bidirectional"))
    )
    (net (code "110") (name "unconnected-(BRAIND-PD10-Pad49)") (class "Default")
      (node (ref "BRAIN") (pin "49") (pinfunction "PD10_49") (pintype "bidirectional"))
    )
    (net (code "111") (name "unconnected-(BRAIND-PD12-Pad51)") (class "Default")
      (node (ref "BRAIN") (pin "51") (pinfunction "PD12_51") (pintype "bidirectional"))
    )
    (net (code "112") (name "unconnected-(BRAIND-PD20-Pad80)") (class "Default")
      (node (ref "BRAIN") (pin "80") (pinfunction "PD20_80") (pintype "bidirectional"))
    )
    (net (code "113") (name "unconnected-(BRAIND-PD21-Pad81)") (class "Default")
      (node (ref "BRAIN") (pin "81") (pinfunction "PD21_81") (pintype "bidirectional"))
    )
    (net (code "114") (name "unconnected-(BRAINE-VSW-Pad117)") (class "Default")
      (node (ref "BRAIN") (pin "117") (pinfunction "VSW_117") (pintype "bidirectional"))
    )
    (net (code "115") (name "unconnected-(RTC-TS(CLK{slash}INTB)-Pad4)") (class "Default")
      (node (ref "RTC") (pin "4") (pinfunction "TS(CLK/INTB)_4") (pintype "bidirectional"))
    )
    (net (code "116") (name "unconnected-(RTC-~{INTA(CLK})-Pad9)") (class "Default")
      (node (ref "RTC") (pin "9") (pinfunction "~{INTA(CLK})_9") (pintype "bidirectional"))
    )
    (net (code "117") (name "unconnected-(SD-PadDAT1)") (class "Default")
      (node (ref "SD") (pin "DAT1") (pinfunction "DAT1_DAT1") (pintype "bidirectional"))
    )
    (net (code "118") (name "unconnected-(SD-PadDAT2)") (class "Default")
      (node (ref "SD") (pin "DAT2") (pinfunction "DAT2_DAT2") (pintype "bidirectional"))
    )
    (net (code "119") (name "unconnected-(SD-PadPAD1)") (class "Default")
      (node (ref "SD") (pin "PAD1") (pinfunction "PAD1_PAD1") (pintype "bidirectional"))
    )
    (net (code "120") (name "unconnected-(SD-PadPAD2)") (class "Default")
      (node (ref "SD") (pin "PAD2") (pinfunction "PAD2_PAD2") (pintype "bidirectional"))
    )
    (net (code "121") (name "unconnected-(SD-PadPAD3)") (class "Default")
      (node (ref "SD") (pin "PAD3") (pinfunction "PAD3_PAD3") (pintype "bidirectional"))
    )
    (net (code "122") (name "unconnected-(SD-PadPAD4)") (class "Default")
      (node (ref "SD") (pin "PAD4") (pinfunction "PAD4_PAD4") (pintype "bidirectional"))
    )
    (net (code "123") (name "unconnected-(SD-PadPAD5)") (class "Default")
      (node (ref "SD") (pin "PAD5") (pinfunction "PAD5_PAD5") (pintype "bidirectional"))
    )
    (net (code "124") (name "unconnected-(SD-PadPAD6)") (class "Default")
      (node (ref "SD") (pin "PAD6") (pinfunction "PAD6_PAD6") (pintype "bidirectional"))
    )
    (net (code "125") (name "unconnected-(U1-~{HOLD}{slash}SO3-PadP$7)") (class "Default")
      (node (ref "U1") (pin "P$7") (pinfunction "~{HOLD}/SO3_P$7") (pintype "bidirectional"))
    )
    (net (code "126") (name "unconnected-(U1-~{WP}{slash}SO2-PadP$3)") (class "Default")
      (node (ref "U1") (pin "P$3") (pinfunction "~{WP}/SO2_P$3") (pintype "bidirectional"))
    )
    (net (code "127") (name "unconnected-(U2-~{HOLD}{slash}SO3-PadP$7)") (class "Default")
      (node (ref "U2") (pin "P$7") (pinfunction "~{HOLD}/SO3_P$7") (pintype "bidirectional"))
    )
    (net (code "128") (name "unconnected-(U2-~{WP}{slash}SO2-PadP$3)") (class "Default")
      (node (ref "U2") (pin "P$3") (pinfunction "~{WP}/SO2_P$3") (pintype "bidirectional"))
    )
    (net (code "129") (name "unconnected-(U3-~{HOLD}{slash}SO3-PadP$7)") (class "Default")
      (node (ref "U3") (pin "P$7") (pinfunction "~{HOLD}/SO3_P$7") (pintype "bidirectional"))
    )
    (net (code "130") (name "unconnected-(U3-~{WP}{slash}SO2-PadP$3)") (class "Default")
      (node (ref "U3") (pin "P$3") (pinfunction "~{WP}/SO2_P$3") (pintype "bidirectional"))
    )
    (net (code "131") (name "unconnected-(U4-~{HOLD}{slash}SO3-PadP$7)") (class "Default")
      (node (ref "U4") (pin "P$7") (pinfunction "~{HOLD}/SO3_P$7") (pintype "bidirectional"))
    )
    (net (code "132") (name "unconnected-(U4-~{WP}{slash}SO2-PadP$3)") (class "Default")
      (node (ref "U4") (pin "P$3") (pinfunction "~{WP}/SO2_P$3") (pintype "bidirectional"))
    )
    (net (code "133") (name "unconnected-(USB-PadPAD1)") (class "Default")
      (node (ref "USB") (pin "PAD1") (pinfunction "PAD1_PAD1") (pintype "bidirectional"))
    )
    (net (code "134") (name "unconnected-(USB-PadPAD2)") (class "Default")
      (node (ref "USB") (pin "PAD2") (pinfunction "PAD2_PAD2") (pintype "bidirectional"))
    )
    (net (code "135") (name "unconnected-(USB-PadPAD3)") (class "Default")
      (node (ref "USB") (pin "PAD3") (pinfunction "PAD3_PAD3") (pintype "bidirectional"))
    )
    (net (code "136") (name "unconnected-(USB-PadPAD4)") (class "Default")
      (node (ref "USB") (pin "PAD4") (pinfunction "PAD4_PAD4") (pintype "bidirectional"))
    )
    (net (code "137") (name "unconnected-(USB-PadPAD5)") (class "Default")
      (node (ref "USB") (pin "PAD5") (pinfunction "PAD5_PAD5") (pintype "bidirectional"))
    )
    (net (code "138") (name "unconnected-(USB-PadPAD6)") (class "Default")
      (node (ref "USB") (pin "PAD6") (pinfunction "PAD6_PAD6") (pintype "bidirectional"))
    )
  )
)
